# cpNode_V3_4.net
KiCad netlist of a schematic drawn in EAGLE
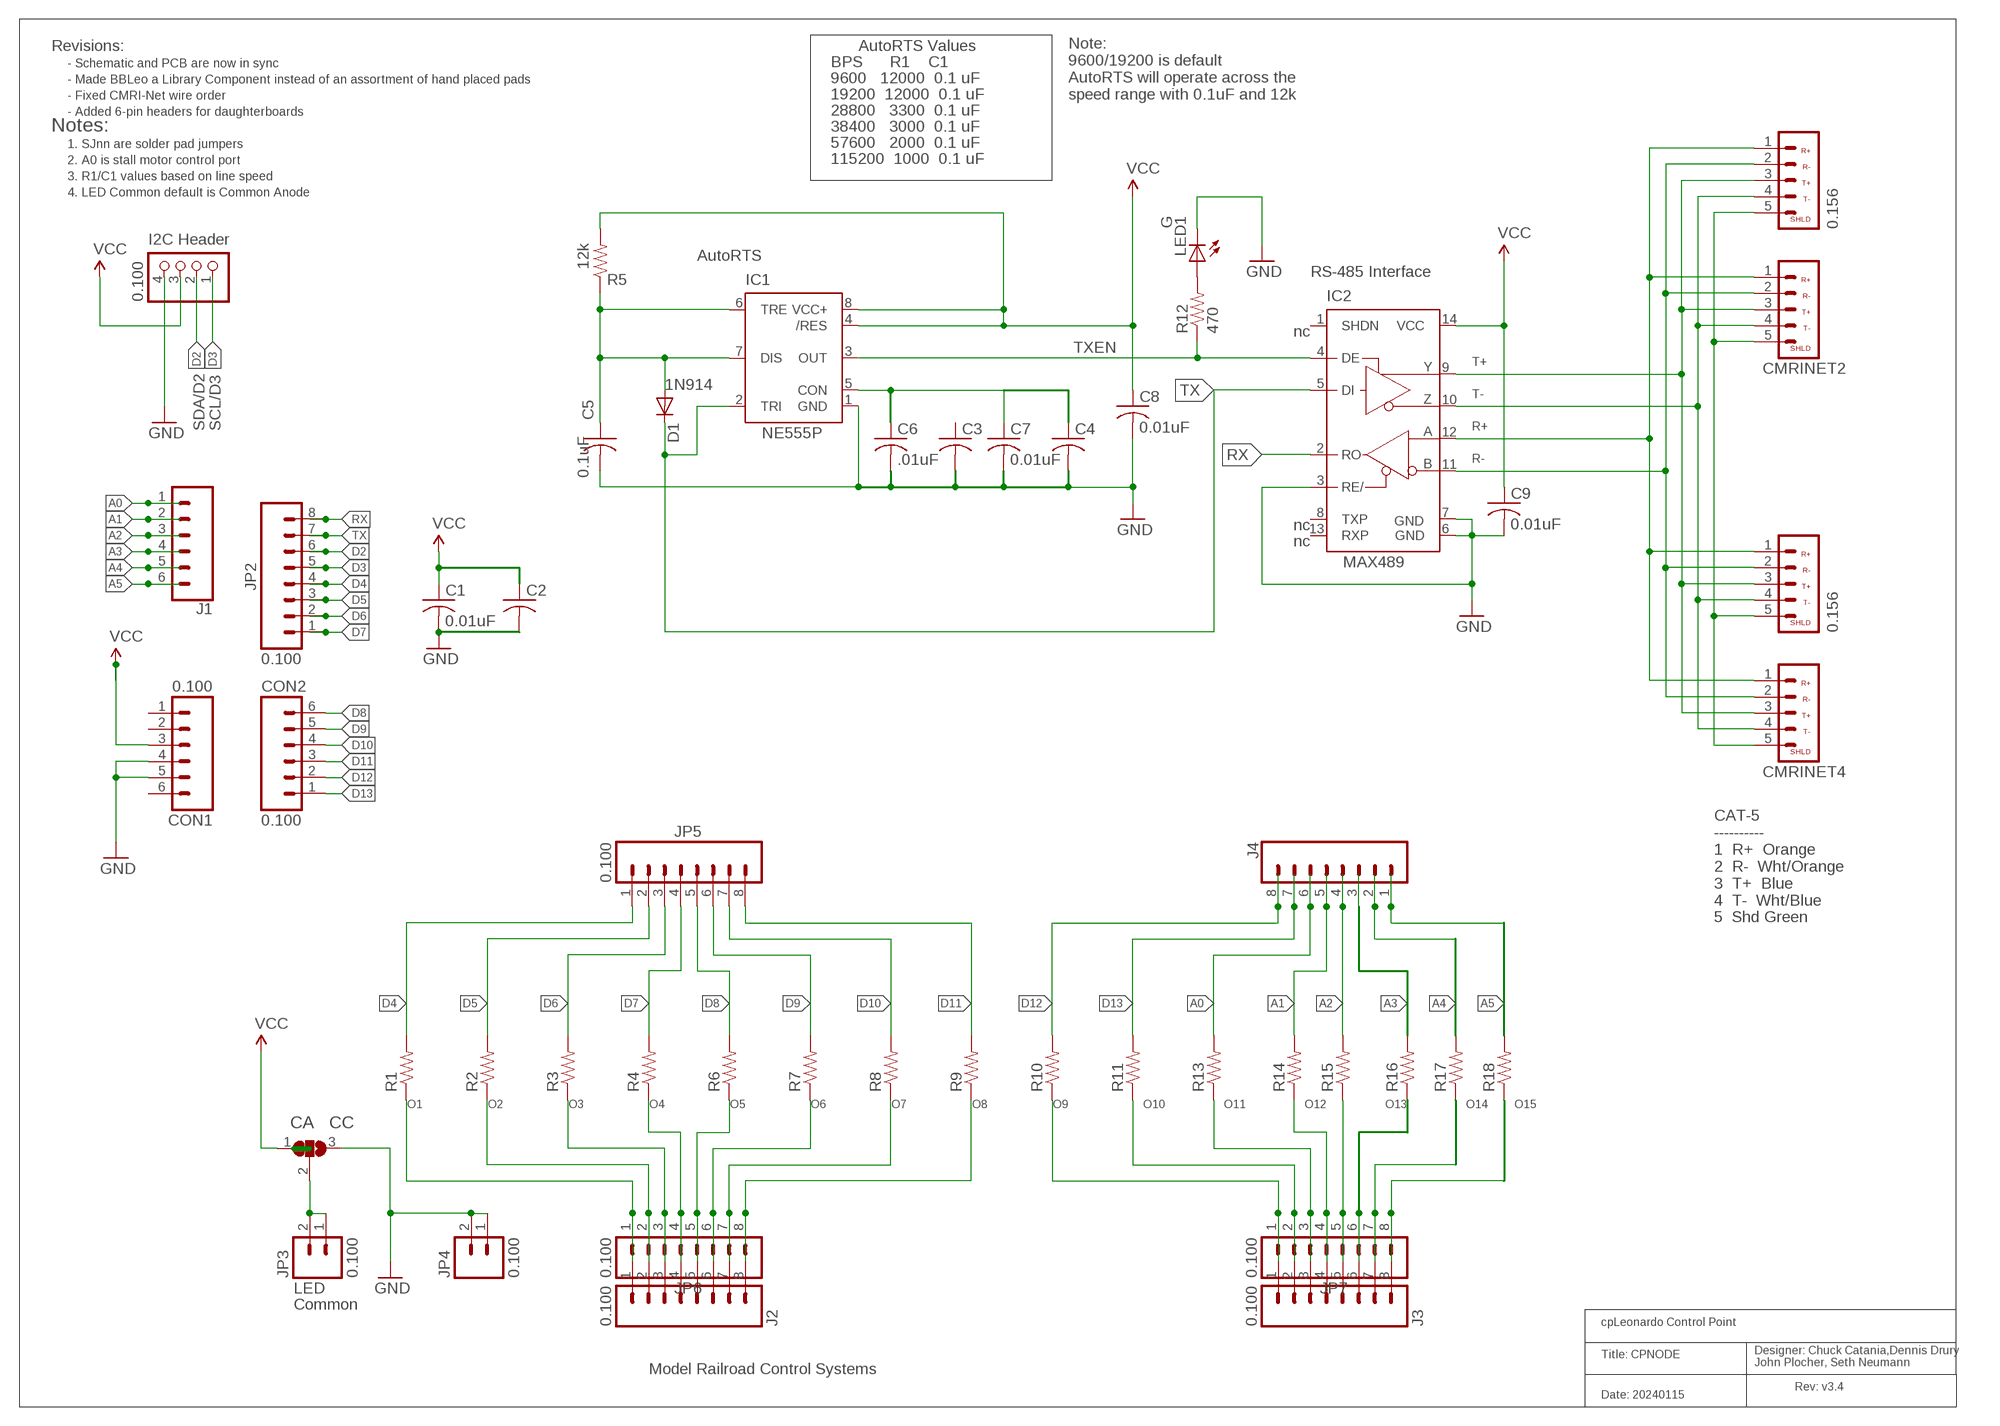
[diagram p0: schematic, sheet 1]

(export (version "E")
  (design (tool "Eeschema 10.0.6"))
  (components
    (comp (ref "C1")
      (value "0.01uF")
      (footprint "eagle-import:C-PTH-0.100")
      (libsource (lib "eagle-import") (part "CAPPTH2"))
    )
    (comp (ref "C2")
      (value "CAPPTH1")
      (footprint "eagle-import:C050-024X044")
      (libsource (lib "eagle-import") (part "CAPPTH1"))
    )
    (comp (ref "C3")
      (value "CAPPTH1")
      (footprint "eagle-import:C050-024X044")
      (libsource (lib "eagle-import") (part "CAPPTH1"))
    )
    (comp (ref "C4")
      (value "CAPPTH1")
      (footprint "eagle-import:C050-024X044")
      (libsource (lib "eagle-import") (part "CAPPTH1"))
    )
    (comp (ref "C5")
      (value "0.1uF")
      (footprint "eagle-import:C-PTH-0.100")
      (libsource (lib "eagle-import") (part "CAPPTH2"))
    )
    (comp (ref "C6")
      (value ".01uF")
      (footprint "eagle-import:C050-024X044")
      (libsource (lib "eagle-import") (part "CAPPTH1"))
    )
    (comp (ref "C7")
      (value "0.01uF")
      (footprint "eagle-import:C-PTH-0.100")
      (libsource (lib "eagle-import") (part "CAPPTH2"))
    )
    (comp (ref "C8")
      (value "0.01uF")
      (footprint "eagle-import:C-PTH-0.100")
      (libsource (lib "eagle-import") (part "CAPPTH2"))
    )
    (comp (ref "C9")
      (value "0.01uF")
      (footprint "eagle-import:C-PTH-0.100")
      (libsource (lib "eagle-import") (part "CAPPTH2"))
    )
    (comp (ref "CMRINET1")
      (value "0.156")
      (footprint "eagle-import:KK-156-5")
      (libsource (lib "eagle-import") (part "CONNECTOR-CMRINET.156"))
    )
    (comp (ref "CMRINET2")
      (value "3.5mm")
      (footprint "eagle-import:CMRINET-3.5MM")
      (libsource (lib "eagle-import") (part "CONNECTOR-CMRINET3.5MM"))
    )
    (comp (ref "CMRINET3")
      (value "0.156")
      (footprint "eagle-import:KK-156-5")
      (libsource (lib "eagle-import") (part "CONNECTOR-CMRINET.156"))
    )
    (comp (ref "CMRINET4")
      (value "3.5mm")
      (footprint "eagle-import:CMRINET-3.5MM")
      (libsource (lib "eagle-import") (part "CONNECTOR-CMRINET3.5MM"))
    )
    (comp (ref "CON1")
      (value "0.100")
      (footprint "eagle-import:1X06-SIP_LOCK")
      (libsource (lib "eagle-import") (part "CONNECTOR-M06SIP_LOCK"))
    )
    (comp (ref "CON2")
      (value "0.100")
      (footprint "eagle-import:1X06-SIP_LOCK")
      (libsource (lib "eagle-import") (part "CONNECTOR-M06SIP_LOCK"))
    )
    (comp (ref "D1")
      (value "1N4148")
      (footprint "eagle-import:DIODE-1N4148")
      (libsource (lib "eagle-import") (part "DIODE1N4148"))
    )
    (comp (ref "IC1")
      (value "NE555P")
      (footprint "eagle-import:DIL-08")
      (fields (field (name "MF") "Arrow Electronics") (field (name "MPN") "NE555N"))
      (libsource (lib "eagle-import") (part "NE555P"))
    )
    (comp (ref "IC2")
      (value "MAX3465CPD")
      (footprint "eagle-import:DIL14")
      (fields (field (name "MPN") "MAX3465CPD+"))
      (libsource (lib "eagle-import") (part "MAX346PD5C"))
    )
    (comp (ref "J1")
      (value "CONN_06SILK_FEMALE_PTH")
      (footprint "eagle-import:1X06")
      (libsource (lib "eagle-import") (part "CONN_06SILK_FEMALE_PTH"))
    )
    (comp (ref "J2")
      (value "0.100")
      (footprint "eagle-import:1X08_LOCK_LONGPADS")
      (libsource (lib "eagle-import") (part "CONNECTOR-M08LOCK_LONGPADS"))
    )
    (comp (ref "J3")
      (value "0.100")
      (footprint "eagle-import:1X08_LOCK_LONGPADS")
      (libsource (lib "eagle-import") (part "CONNECTOR-M08LOCK_LONGPADS"))
    )
    (comp (ref "J4")
      (value "CONN_08\"")
      (footprint "eagle-import:1X08")
      (libsource (lib "eagle-import") (part "CONN_08{dblquote}"))
    )
    (comp (ref "JP1")
      (value "0.100")
      (footprint "eagle-import:1X04_90")
      (libsource (lib "eagle-import") (part "PINHD-1X4/90"))
    )
    (comp (ref "JP2")
      (value "0.100")
      (footprint "eagle-import:1X08")
      (libsource (lib "eagle-import") (part "M081X08"))
    )
    (comp (ref "JP3")
      (value "0.100")
      (footprint "eagle-import:MOLEX-1X2_LOCK")
      (libsource (lib "eagle-import") (part "M02POLAR_LOCK"))
    )
    (comp (ref "JP4")
      (value "0.100")
      (footprint "eagle-import:MOLEX-1X2_LOCK")
      (libsource (lib "eagle-import") (part "M02POLAR_LOCK"))
    )
    (comp (ref "JP5")
      (value "0.100")
      (footprint "eagle-import:1X08")
      (libsource (lib "eagle-import") (part "M081X08"))
    )
    (comp (ref "JP6")
      (value "0.100")
      (footprint "eagle-import:1X08")
      (libsource (lib "eagle-import") (part "M081X08"))
    )
    (comp (ref "JP7")
      (value "0.100")
      (footprint "eagle-import:1X08")
      (libsource (lib "eagle-import") (part "M081X08"))
    )
    (comp (ref "LED1")
      (value "G")
      (footprint "eagle-import:LED3MM")
      (libsource (lib "eagle-import") (part "LEDLED3MM"))
    )
    (comp (ref "P1")
      (value "CA CC")
      (footprint "eagle-import:3P-SMD-2X4.8")
      (libsource (lib "eagle-import") (part "PAD-SOLDERJUMPER-2WAYT"))
    )
    (comp (ref "R1")
      (value "RPTH-R0")
      (footprint "eagle-import:CUT-R")
      (libsource (lib "eagle-import") (part "RPTH-R0"))
    )
    (comp (ref "R2")
      (value "RPTH-R0")
      (footprint "eagle-import:CUT-R")
      (libsource (lib "eagle-import") (part "RPTH-R0"))
    )
    (comp (ref "R3")
      (value "RPTH-R0")
      (footprint "eagle-import:CUT-R")
      (libsource (lib "eagle-import") (part "RPTH-R0"))
    )
    (comp (ref "R4")
      (value "RPTH-R0")
      (footprint "eagle-import:CUT-R")
      (libsource (lib "eagle-import") (part "RPTH-R0"))
    )
    (comp (ref "R5")
      (value "12k")
      (footprint "eagle-import:AXIAL-0.4-RES")
      (libsource (lib "eagle-import") (part "RPTH04"))
    )
    (comp (ref "R6")
      (value "RPTH-R0")
      (footprint "eagle-import:CUT-R")
      (libsource (lib "eagle-import") (part "RPTH-R0"))
    )
    (comp (ref "R7")
      (value "RPTH-R0")
      (footprint "eagle-import:CUT-R")
      (libsource (lib "eagle-import") (part "RPTH-R0"))
    )
    (comp (ref "R8")
      (value "RPTH-R0")
      (footprint "eagle-import:CUT-R")
      (libsource (lib "eagle-import") (part "RPTH-R0"))
    )
    (comp (ref "R9")
      (value "RPTH-R0")
      (footprint "eagle-import:CUT-R")
      (libsource (lib "eagle-import") (part "RPTH-R0"))
    )
    (comp (ref "R10")
      (value "RPTH-R0")
      (footprint "eagle-import:CUT-R")
      (libsource (lib "eagle-import") (part "RPTH-R0"))
    )
    (comp (ref "R11")
      (value "RPTH-R0")
      (footprint "eagle-import:CUT-R")
      (libsource (lib "eagle-import") (part "RPTH-R0"))
    )
    (comp (ref "R12")
      (value "470")
      (footprint "eagle-import:AXIAL-0.4-RES")
      (libsource (lib "eagle-import") (part "RPTH04"))
    )
    (comp (ref "R13")
      (value "RPTH-R0")
      (footprint "eagle-import:CUT-R")
      (libsource (lib "eagle-import") (part "RPTH-R0"))
    )
    (comp (ref "R14")
      (value "RPTH-R0")
      (footprint "eagle-import:CUT-R")
      (libsource (lib "eagle-import") (part "RPTH-R0"))
    )
    (comp (ref "R15")
      (value "RPTH-R0")
      (footprint "eagle-import:CUT-R")
      (libsource (lib "eagle-import") (part "RPTH-R0"))
    )
    (comp (ref "R16")
      (value "RPTH-R0")
      (footprint "eagle-import:CUT-R")
      (libsource (lib "eagle-import") (part "RPTH-R0"))
    )
    (comp (ref "R17")
      (value "RPTH-R0")
      (footprint "eagle-import:CUT-R")
      (libsource (lib "eagle-import") (part "RPTH-R0"))
    )
    (comp (ref "R18")
      (value "RPTH-R0")
      (footprint "eagle-import:CUT-R")
      (libsource (lib "eagle-import") (part "RPTH-R0"))
    )
  )
  (nets
    (net (code "1") (name "/O1") (class "Default")
      (node (ref "J2") (pin "1") (pinfunction "1_1") (pintype "passive"))
      (node (ref "JP6") (pin "1") (pinfunction "1_1") (pintype "passive"))
      (node (ref "R1") (pin "P2") (pinfunction "1_P2") (pintype "passive"))
    )
    (net (code "2") (name "/O2") (class "Default")
      (node (ref "J2") (pin "2") (pinfunction "2_2") (pintype "passive"))
      (node (ref "JP6") (pin "2") (pinfunction "2_2") (pintype "passive"))
      (node (ref "R2") (pin "P2") (pinfunction "1_P2") (pintype "passive"))
    )
    (net (code "3") (name "/O3") (class "Default")
      (node (ref "J2") (pin "3") (pinfunction "3_3") (pintype "passive"))
      (node (ref "JP6") (pin "3") (pinfunction "3_3") (pintype "passive"))
      (node (ref "R3") (pin "P2") (pinfunction "1_P2") (pintype "passive"))
    )
    (net (code "4") (name "/O4") (class "Default")
      (node (ref "J2") (pin "4") (pinfunction "4_4") (pintype "passive"))
      (node (ref "JP6") (pin "4") (pinfunction "4_4") (pintype "passive"))
      (node (ref "R4") (pin "P2") (pinfunction "1_P2") (pintype "passive"))
    )
    (net (code "5") (name "/O5") (class "Default")
      (node (ref "J2") (pin "5") (pinfunction "5_5") (pintype "passive"))
      (node (ref "JP6") (pin "5") (pinfunction "5_5") (pintype "passive"))
      (node (ref "R6") (pin "P2") (pinfunction "1_P2") (pintype "passive"))
    )
    (net (code "6") (name "/O6") (class "Default")
      (node (ref "J2") (pin "6") (pinfunction "6_6") (pintype "passive"))
      (node (ref "JP6") (pin "6") (pinfunction "6_6") (pintype "passive"))
      (node (ref "R7") (pin "P2") (pinfunction "1_P2") (pintype "passive"))
    )
    (net (code "7") (name "/O7") (class "Default")
      (node (ref "J2") (pin "7") (pinfunction "7_7") (pintype "passive"))
      (node (ref "JP6") (pin "7") (pinfunction "7_7") (pintype "passive"))
      (node (ref "R8") (pin "P2") (pinfunction "1_P2") (pintype "passive"))
    )
    (net (code "8") (name "/O8") (class "Default")
      (node (ref "J2") (pin "8") (pinfunction "8_8") (pintype "passive"))
      (node (ref "JP6") (pin "8") (pinfunction "8_8") (pintype "passive"))
      (node (ref "R9") (pin "P2") (pinfunction "1_P2") (pintype "passive"))
    )
    (net (code "9") (name "/O9") (class "Default")
      (node (ref "J3") (pin "1") (pinfunction "1_1") (pintype "passive"))
      (node (ref "JP7") (pin "1") (pinfunction "1_1") (pintype "passive"))
      (node (ref "R10") (pin "P2") (pinfunction "1_P2") (pintype "passive"))
    )
    (net (code "10") (name "/O10") (class "Default")
      (node (ref "J3") (pin "2") (pinfunction "2_2") (pintype "passive"))
      (node (ref "JP7") (pin "2") (pinfunction "2_2") (pintype "passive"))
      (node (ref "R11") (pin "P2") (pinfunction "1_P2") (pintype "passive"))
    )
    (net (code "11") (name "/O11") (class "Default")
      (node (ref "J3") (pin "3") (pinfunction "3_3") (pintype "passive"))
      (node (ref "JP7") (pin "3") (pinfunction "3_3") (pintype "passive"))
      (node (ref "R13") (pin "P2") (pinfunction "1_P2") (pintype "passive"))
    )
    (net (code "12") (name "/O12") (class "Default")
      (node (ref "J3") (pin "4") (pinfunction "4_4") (pintype "passive"))
      (node (ref "JP7") (pin "4") (pinfunction "4_4") (pintype "passive"))
      (node (ref "R14") (pin "P2") (pinfunction "1_P2") (pintype "passive"))
    )
    (net (code "13") (name "/O13") (class "Default")
      (node (ref "J3") (pin "5") (pinfunction "5_5") (pintype "passive"))
      (node (ref "JP7") (pin "5") (pinfunction "5_5") (pintype "passive"))
      (node (ref "R15") (pin "P2") (pinfunction "1_P2") (pintype "passive"))
    )
    (net (code "14") (name "/O14") (class "Default")
      (node (ref "J3") (pin "6") (pinfunction "6_6") (pintype "passive"))
      (node (ref "JP7") (pin "6") (pinfunction "6_6") (pintype "passive"))
      (node (ref "R16") (pin "P2") (pinfunction "1_P2") (pintype "passive"))
    )
    (net (code "15") (name "/O15") (class "Default")
      (node (ref "J3") (pin "7") (pinfunction "7_7") (pintype "passive"))
      (node (ref "JP7") (pin "7") (pinfunction "7_7") (pintype "passive"))
      (node (ref "R17") (pin "P2") (pinfunction "1_P2") (pintype "passive"))
    )
    (net (code "16") (name "A0") (class "Default")
      (node (ref "J1") (pin "1") (pinfunction "1_1") (pintype "passive"))
      (node (ref "J4") (pin "6") (pinfunction "6_6") (pintype "passive"))
      (node (ref "R13") (pin "P1") (pinfunction "2_P1") (pintype "passive"))
    )
    (net (code "17") (name "A1") (class "Default")
      (node (ref "J1") (pin "2") (pinfunction "2_2") (pintype "passive"))
      (node (ref "J4") (pin "5") (pinfunction "5_5") (pintype "passive"))
      (node (ref "R14") (pin "P1") (pinfunction "2_P1") (pintype "passive"))
    )
    (net (code "18") (name "A2") (class "Default")
      (node (ref "J1") (pin "3") (pinfunction "3_3") (pintype "passive"))
      (node (ref "J4") (pin "4") (pinfunction "4_4") (pintype "passive"))
      (node (ref "R15") (pin "P1") (pinfunction "2_P1") (pintype "passive"))
    )
    (net (code "19") (name "A3") (class "Default")
      (node (ref "J1") (pin "4") (pinfunction "4_4") (pintype "passive"))
      (node (ref "J4") (pin "3") (pinfunction "3_3") (pintype "passive"))
      (node (ref "R16") (pin "P1") (pinfunction "2_P1") (pintype "passive"))
    )
    (net (code "20") (name "A4") (class "Default")
      (node (ref "J1") (pin "5") (pinfunction "5_5") (pintype "passive"))
      (node (ref "J4") (pin "2") (pinfunction "2_2") (pintype "passive"))
      (node (ref "R17") (pin "P1") (pinfunction "2_P1") (pintype "passive"))
    )
    (net (code "21") (name "A5") (class "Default")
      (node (ref "J1") (pin "6") (pinfunction "6_6") (pintype "passive"))
      (node (ref "J4") (pin "1") (pinfunction "1_1") (pintype "passive"))
      (node (ref "R18") (pin "P1") (pinfunction "2_P1") (pintype "passive"))
    )
    (net (code "22") (name "D2") (class "Default")
      (node (ref "JP1") (pin "2") (pinfunction "2_2") (pintype "passive"))
      (node (ref "JP2") (pin "6") (pinfunction "6_6") (pintype "passive"))
    )
    (net (code "23") (name "D3") (class "Default")
      (node (ref "JP1") (pin "1") (pinfunction "1_1") (pintype "passive"))
      (node (ref "JP2") (pin "5") (pinfunction "5_5") (pintype "passive"))
    )
    (net (code "24") (name "D4") (class "Default")
      (node (ref "JP2") (pin "4") (pinfunction "4_4") (pintype "passive"))
      (node (ref "JP5") (pin "1") (pinfunction "1_1") (pintype "passive"))
      (node (ref "R1") (pin "P1") (pinfunction "2_P1") (pintype "passive"))
    )
    (net (code "25") (name "D5") (class "Default")
      (node (ref "JP2") (pin "3") (pinfunction "3_3") (pintype "passive"))
      (node (ref "JP5") (pin "2") (pinfunction "2_2") (pintype "passive"))
      (node (ref "R2") (pin "P1") (pinfunction "2_P1") (pintype "passive"))
    )
    (net (code "26") (name "D6") (class "Default")
      (node (ref "JP2") (pin "2") (pinfunction "2_2") (pintype "passive"))
      (node (ref "JP5") (pin "3") (pinfunction "3_3") (pintype "passive"))
      (node (ref "R3") (pin "P1") (pinfunction "2_P1") (pintype "passive"))
    )
    (net (code "27") (name "D7") (class "Default")
      (node (ref "JP2") (pin "1") (pinfunction "1_1") (pintype "passive"))
      (node (ref "JP5") (pin "4") (pinfunction "4_4") (pintype "passive"))
      (node (ref "R4") (pin "P1") (pinfunction "2_P1") (pintype "passive"))
    )
    (net (code "28") (name "D8") (class "Default")
      (node (ref "CON2") (pin "6") (pinfunction "6_6") (pintype "passive"))
      (node (ref "JP5") (pin "5") (pinfunction "5_5") (pintype "passive"))
      (node (ref "R6") (pin "P1") (pinfunction "2_P1") (pintype "passive"))
    )
    (net (code "29") (name "D9") (class "Default")
      (node (ref "CON2") (pin "5") (pinfunction "5_5") (pintype "passive"))
      (node (ref "JP5") (pin "6") (pinfunction "6_6") (pintype "passive"))
      (node (ref "R7") (pin "P1") (pinfunction "2_P1") (pintype "passive"))
    )
    (net (code "30") (name "D10") (class "Default")
      (node (ref "CON2") (pin "4") (pinfunction "4_4") (pintype "passive"))
      (node (ref "JP5") (pin "7") (pinfunction "7_7") (pintype "passive"))
      (node (ref "R8") (pin "P1") (pinfunction "2_P1") (pintype "passive"))
    )
    (net (code "31") (name "D11") (class "Default")
      (node (ref "CON2") (pin "3") (pinfunction "3_3") (pintype "passive"))
      (node (ref "JP5") (pin "8") (pinfunction "8_8") (pintype "passive"))
      (node (ref "R9") (pin "P1") (pinfunction "2_P1") (pintype "passive"))
    )
    (net (code "32") (name "D12") (class "Default")
      (node (ref "CON2") (pin "2") (pinfunction "2_2") (pintype "passive"))
      (node (ref "J4") (pin "8") (pinfunction "8_8") (pintype "passive"))
      (node (ref "R10") (pin "P1") (pinfunction "2_P1") (pintype "passive"))
    )
    (net (code "33") (name "D13") (class "Default")
      (node (ref "CON2") (pin "1") (pinfunction "1_1") (pintype "passive"))
      (node (ref "J4") (pin "7") (pinfunction "7_7") (pintype "passive"))
      (node (ref "R11") (pin "P1") (pinfunction "2_P1") (pintype "passive"))
    )
    (net (code "34") (name "GND") (class "Default")
      (node (ref "C1") (pin "2") (pinfunction "2_2") (pintype "passive"))
      (node (ref "C2") (pin "2") (pinfunction "2_2") (pintype "passive"))
      (node (ref "C3") (pin "2") (pinfunction "2_2") (pintype "passive"))
      (node (ref "C4") (pin "2") (pinfunction "2_2") (pintype "passive"))
      (node (ref "C5") (pin "2") (pinfunction "2_2") (pintype "passive"))
      (node (ref "C6") (pin "2") (pinfunction "2_2") (pintype "passive"))
      (node (ref "C7") (pin "2") (pinfunction "2_2") (pintype "passive"))
      (node (ref "C8") (pin "2") (pinfunction "2_2") (pintype "passive"))
      (node (ref "C9") (pin "2") (pinfunction "2_2") (pintype "passive"))
      (node (ref "CON1") (pin "4") (pinfunction "4_4") (pintype "passive"))
      (node (ref "CON1") (pin "5") (pinfunction "5_5") (pintype "passive"))
      (node (ref "IC1") (pin "1") (pinfunction "GND_1") (pintype "power_in"))
      (node (ref "IC2") (pin "3") (pinfunction "RE/_3") (pintype "input"))
      (node (ref "IC2") (pin "6") (pinfunction "GND_6") (pintype "power_in"))
      (node (ref "IC2") (pin "7") (pinfunction "GND_7") (pintype "power_in"))
      (node (ref "JP1") (pin "4") (pinfunction "4_4") (pintype "passive"))
      (node (ref "JP4") (pin "1") (pinfunction "1_1") (pintype "passive"))
      (node (ref "JP4") (pin "2") (pinfunction "2_2") (pintype "passive"))
      (node (ref "LED1") (pin "K") (pinfunction "C_K") (pintype "passive"))
      (node (ref "P1") (pin "3") (pinfunction "3_3") (pintype "passive"))
    )
    (net (code "35") (name "Net-(CMRINET1-Pad5)") (class "Default")
      (node (ref "CMRINET1") (pin "5") (pinfunction "5_5") (pintype "passive"))
      (node (ref "CMRINET2") (pin "5") (pinfunction "5_5") (pintype "passive"))
      (node (ref "CMRINET3") (pin "5") (pinfunction "5_5") (pintype "passive"))
      (node (ref "CMRINET4") (pin "5") (pinfunction "5_5") (pintype "passive"))
    )
    (net (code "36") (name "Net-(IC1-CON)") (class "Default")
      (node (ref "C4") (pin "1") (pinfunction "1_1") (pintype "passive"))
      (node (ref "C6") (pin "1") (pinfunction "1_1") (pintype "passive"))
      (node (ref "C7") (pin "1") (pinfunction "1_1") (pintype "passive"))
      (node (ref "IC1") (pin "5") (pinfunction "CON_5") (pintype "input"))
    )
    (net (code "37") (name "Net-(IC1-DIS)") (class "Default")
      (node (ref "C5") (pin "1") (pinfunction "1_1") (pintype "passive"))
      (node (ref "D1") (pin "A") (pinfunction "A_A") (pintype "passive"))
      (node (ref "IC1") (pin "6") (pinfunction "TRE_6") (pintype "input"))
      (node (ref "IC1") (pin "7") (pinfunction "DIS_7") (pintype "input"))
      (node (ref "R5") (pin "P$1") (pinfunction "1_P$1") (pintype "passive"))
    )
    (net (code "38") (name "Net-(IC1-OUT)") (class "Default")
      (node (ref "IC1") (pin "3") (pinfunction "OUT_3") (pintype "output"))
      (node (ref "IC2") (pin "4") (pinfunction "DE_4") (pintype "input"))
      (node (ref "R12") (pin "P$1") (pinfunction "1_P$1") (pintype "passive"))
    )
    (net (code "39") (name "Net-(IC2-A)") (class "Default")
      (node (ref "CMRINET1") (pin "1") (pinfunction "1_1") (pintype "passive"))
      (node (ref "CMRINET2") (pin "1") (pinfunction "1_1") (pintype "passive"))
      (node (ref "CMRINET3") (pin "1") (pinfunction "1_1") (pintype "passive"))
      (node (ref "CMRINET4") (pin "1") (pinfunction "1_1") (pintype "passive"))
      (node (ref "IC2") (pin "12") (pinfunction "A_12") (pintype "input"))
    )
    (net (code "40") (name "Net-(IC2-B)") (class "Default")
      (node (ref "CMRINET1") (pin "2") (pinfunction "2_2") (pintype "passive"))
      (node (ref "CMRINET2") (pin "2") (pinfunction "2_2") (pintype "passive"))
      (node (ref "CMRINET3") (pin "2") (pinfunction "2_2") (pintype "passive"))
      (node (ref "CMRINET4") (pin "2") (pinfunction "2_2") (pintype "passive"))
      (node (ref "IC2") (pin "11") (pinfunction "B_11") (pintype "input"))
    )
    (net (code "41") (name "Net-(IC2-Y)") (class "Default")
      (node (ref "CMRINET1") (pin "3") (pinfunction "3_3") (pintype "passive"))
      (node (ref "CMRINET2") (pin "3") (pinfunction "3_3") (pintype "passive"))
      (node (ref "CMRINET3") (pin "3") (pinfunction "3_3") (pintype "passive"))
      (node (ref "CMRINET4") (pin "3") (pinfunction "3_3") (pintype "passive"))
      (node (ref "IC2") (pin "9") (pinfunction "Y_9") (pintype "output"))
    )
    (net (code "42") (name "Net-(IC2-Z)") (class "Default")
      (node (ref "CMRINET1") (pin "4") (pinfunction "4_4") (pintype "passive"))
      (node (ref "CMRINET2") (pin "4") (pinfunction "4_4") (pintype "passive"))
      (node (ref "CMRINET3") (pin "4") (pinfunction "4_4") (pintype "passive"))
      (node (ref "CMRINET4") (pin "4") (pinfunction "4_4") (pintype "passive"))
      (node (ref "IC2") (pin "10") (pinfunction "Z_10") (pintype "output"))
    )
    (net (code "43") (name "Net-(JP3-Pad1)") (class "Default")
      (node (ref "JP3") (pin "1") (pinfunction "1_1") (pintype "passive"))
      (node (ref "JP3") (pin "2") (pinfunction "2_2") (pintype "passive"))
      (node (ref "P1") (pin "2") (pinfunction "2_2") (pintype "passive"))
    )
    (net (code "44") (name "Net-(R12-2)") (class "Default")
      (node (ref "LED1") (pin "A") (pinfunction "A_A") (pintype "passive"))
      (node (ref "R12") (pin "P$2") (pinfunction "2_P$2") (pintype "passive"))
    )
    (net (code "45") (name "Net-(R18-1)") (class "Default")
      (node (ref "J3") (pin "8") (pinfunction "8_8") (pintype "passive"))
      (node (ref "JP7") (pin "8") (pinfunction "8_8") (pintype "passive"))
      (node (ref "R18") (pin "P2") (pinfunction "1_P2") (pintype "passive"))
    )
    (net (code "46") (name "RX") (class "Default")
      (node (ref "IC2") (pin "2") (pinfunction "RO_2") (pintype "output"))
      (node (ref "JP2") (pin "8") (pinfunction "8_8") (pintype "passive"))
    )
    (net (code "47") (name "TX") (class "Default")
      (node (ref "D1") (pin "C") (pinfunction "C_C") (pintype "passive"))
      (node (ref "IC1") (pin "2") (pinfunction "TRI_2") (pintype "input"))
      (node (ref "IC2") (pin "5") (pinfunction "DI_5") (pintype "input"))
      (node (ref "JP2") (pin "7") (pinfunction "7_7") (pintype "passive"))
    )
    (net (code "48") (name "VCC") (class "Default")
      (node (ref "C1") (pin "1") (pinfunction "1_1") (pintype "passive"))
      (node (ref "C2") (pin "1") (pinfunction "1_1") (pintype "passive"))
      (node (ref "C8") (pin "1") (pinfunction "1_1") (pintype "passive"))
      (node (ref "C9") (pin "1") (pinfunction "1_1") (pintype "passive"))
      (node (ref "CON1") (pin "3") (pinfunction "3_3") (pintype "passive"))
      (node (ref "IC1") (pin "4") (pinfunction "/RES_4") (pintype "input"))
      (node (ref "IC1") (pin "8") (pinfunction "VCC+_8") (pintype "power_in"))
      (node (ref "IC2") (pin "14") (pinfunction "VCC_14") (pintype "power_in"))
      (node (ref "JP1") (pin "3") (pinfunction "3_3") (pintype "passive"))
      (node (ref "P1") (pin "1") (pinfunction "1_1") (pintype "passive"))
      (node (ref "R5") (pin "P$2") (pinfunction "2_P$2") (pintype "passive"))
    )
    (net (code "49") (name "unconnected-(C3-Pad1)") (class "Default")
      (node (ref "C3") (pin "1") (pinfunction "1_1") (pintype "passive"))
    )
    (net (code "50") (name "unconnected-(CON1-Pad1)") (class "Default")
      (node (ref "CON1") (pin "1") (pinfunction "1_1") (pintype "passive"))
    )
    (net (code "51") (name "unconnected-(CON1-Pad2)") (class "Default")
      (node (ref "CON1") (pin "2") (pinfunction "2_2") (pintype "passive"))
    )
    (net (code "52") (name "unconnected-(CON1-Pad6)") (class "Default")
      (node (ref "CON1") (pin "6") (pinfunction "6_6") (pintype "passive"))
    )
    (net (code "53") (name "unconnected-(IC2-RXP-Pad13)") (class "Default")
      (node (ref "IC2") (pin "13") (pinfunction "RXP_13") (pintype "passive"))
    )
    (net (code "54") (name "unconnected-(IC2-SHDN-Pad1)") (class "Default")
      (node (ref "IC2") (pin "1") (pinfunction "SHDN_1") (pintype "input"))
    )
    (net (code "55") (name "unconnected-(IC2-TXP-Pad8)") (class "Default")
      (node (ref "IC2") (pin "8") (pinfunction "TXP_8") (pintype "passive"))
    )
  )
)
